# PWRSUPPLY.net
KiCad netlist of a schematic drawn in Altium Designer
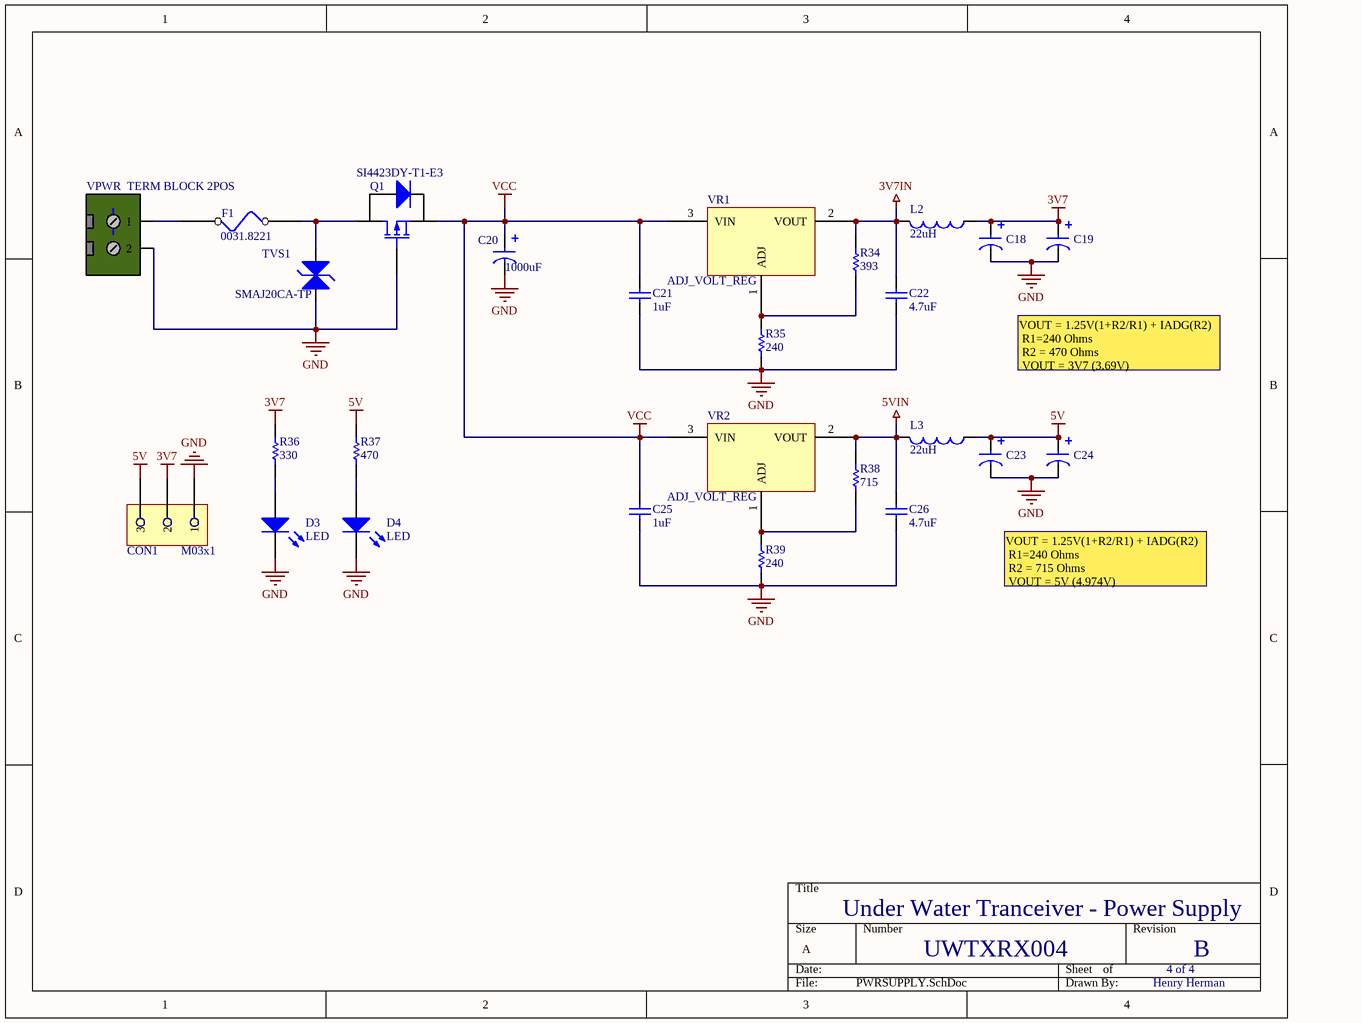
[diagram p0: PWRSUPPLY.SchDoc]

(export (version "E")
  (design (tool "Eeschema 10.0.6"))
  (components
    (comp (ref "C18")
      (value "CAP_POL")
      (footprint "SM/C_POL_0805")
      (description "CAP")
      (libsource (lib "Henry1_20_2010") (part "CAP_POL"))
    )
    (comp (ref "C19")
      (value "CAP_POL")
      (footprint "SM/C_POL_0805")
      (description "CAP")
      (libsource (lib "Henry1_20_2010") (part "CAP_POL"))
    )
    (comp (ref "C20")
      (value "CAP_POL")
      (footprint "CAP-CAN-SMD-POL-12.5mmDia")
      (description "CAP")
      (fields (field (name "LABEL") "1000uF"))
      (libsource (lib "Henry1_20_2010") (part "CAP_POL"))
    )
    (comp (ref "C21")
      (value "1uF")
      (footprint "SM/C_0805")
      (description "CAP")
      (libsource (lib "Henry1_20_2010") (part "CAP"))
    )
    (comp (ref "C22")
      (value "4.7uF")
      (footprint "SM/C_0805")
      (description "CAP")
      (libsource (lib "Henry1_20_2010") (part "CAP"))
    )
    (comp (ref "C23")
      (value "CAP_POL")
      (footprint "SM/C_POL_0805")
      (description "CAP")
      (libsource (lib "Henry1_20_2010") (part "CAP_POL"))
    )
    (comp (ref "C24")
      (value "CAP_POL")
      (footprint "SM/C_POL_0805")
      (description "CAP")
      (libsource (lib "Henry1_20_2010") (part "CAP_POL"))
    )
    (comp (ref "C25")
      (value "1uF")
      (footprint "SM/C_0805")
      (description "CAP")
      (libsource (lib "Henry1_20_2010") (part "CAP"))
    )
    (comp (ref "C26")
      (value "4.7uF")
      (footprint "SM/C_0805")
      (description "CAP")
      (libsource (lib "Henry1_20_2010") (part "CAP"))
    )
    (comp (ref "CON1") (value "M03x1") (footprint "M03x1") (libsource (lib "Henry1_20_2010") (part "M03x1")))
    (comp (ref "D3") (value "LED") (footprint "LED-0805") (libsource (lib "Henry1_20_2010") (part "LED")))
    (comp (ref "D4") (value "LED") (footprint "LED-0805") (libsource (lib "Henry1_20_2010") (part "LED")))
    (comp (ref "F1")
      (value "0031.8221")
      (footprint "SCHURTER/SMD/2 PADS/0031.8221")
      (description "FUSEHOLDER BLACK FOR SMD 5X20MM")
      (libsource (lib "FriedParts") (part "FUSE"))
    )
    (comp (ref "L2")
      (value "22uH")
      (footprint "G_JMETRIC/TDK/SLE10145")
      (description "INDUCTOR SHIELD PWR 22UH 10145")
      (fields (field (name "MFRPARTNUM") "SLF10145T-220M1R9-PF"))
      (libsource (lib "FriedParts") (part "INDUCTOR"))
    )
    (comp (ref "L3")
      (value "22uH")
      (footprint "G_JMETRIC/TDK/SLE10145")
      (description "INDUCTOR SHIELD PWR 22UH 10145")
      (fields (field (name "MFRPARTNUM") "SLF10145T-220M1R9-PF"))
      (libsource (lib "FriedParts") (part "INDUCTOR"))
    )
    (comp (ref "Q1")
      (value "SI4423DY-T1-E3")
      (footprint "SOIC-8-Lead-Vishay-PFET")
      (description "mosfet,p ch,20v,10a,8soic; transistor polarity:p channel;")
      (libsource (lib "FriedParts") (part "P-Channel 20V D-S MOSFET"))
    )
    (comp (ref "R34")
      (value "393")
      (footprint "SM/R_0805")
      (description "Resistor")
      (fields (field (name "Comment") "Res") (field (name "PUBLISHER") "Altium Limited"))
      (libsource (lib "Henry1_20_2010") (part "Res"))
    )
    (comp (ref "R35")
      (value "240")
      (footprint "SM/R_0805")
      (description "Resistor")
      (fields (field (name "Comment") "Res") (field (name "PUBLISHER") "Altium Limited"))
      (libsource (lib "Henry1_20_2010") (part "Res"))
    )
    (comp (ref "R36")
      (value "330")
      (footprint "SM/R_0805")
      (description "Resistor")
      (fields (field (name "Comment") "Res") (field (name "PUBLISHER") "Altium Limited"))
      (libsource (lib "Henry1_20_2010") (part "Res"))
    )
    (comp (ref "R37")
      (value "470")
      (footprint "SM/R_0805")
      (description "Resistor")
      (fields (field (name "Comment") "Res") (field (name "PUBLISHER") "Altium Limited"))
      (libsource (lib "Henry1_20_2010") (part "Res"))
    )
    (comp (ref "R38")
      (value "715")
      (footprint "SM/R_0805")
      (description "Resistor")
      (fields (field (name "Comment") "Res") (field (name "PUBLISHER") "Altium Limited"))
      (libsource (lib "Henry1_20_2010") (part "Res"))
    )
    (comp (ref "R39")
      (value "240")
      (footprint "SM/R_0805")
      (description "Resistor")
      (fields (field (name "Comment") "Res") (field (name "PUBLISHER") "Altium Limited"))
      (libsource (lib "Henry1_20_2010") (part "Res"))
    )
    (comp (ref "TVS1")
      (value "SMAJ20CA-TP")
      (footprint "D0-214AC")
      (description "TVS 400W 12V BIDIRECT SMA")
      (fields (field (name "MFRPARTNUM") "SMAJ12CA-TP"))
      (libsource (lib "FriedParts") (part "SMAJ12CA-TPMC"))
    )
    (comp (ref "VPWR")
      (value "TERM BLOCK 2POS")
      (footprint "Conn-ScrewTerminal-2pin-Phoenix")
      (libsource (lib "Henry1_20_2010") (part "2Pin-PhoenixTerminalBlock"))
    )
    (comp (ref "VR1")
      (value "ADJ_VOLT_REG")
      (footprint "LM317-SOT233-POS-ADJ-VOLT_REG")
      (libsource (lib "Henry1_20_2010") (part "ADJ_VOLT_REG"))
    )
    (comp (ref "VR2")
      (value "ADJ_VOLT_REG")
      (footprint "LM317-SOT233-POS-ADJ-VOLT_REG")
      (libsource (lib "Henry1_20_2010") (part "ADJ_VOLT_REG"))
    )
  )
  (nets
    (net (code "1") (name "3V7") (class "Default")
      (node (ref "C18") (pin "1") (pinfunction "1_1") (pintype "passive"))
      (node (ref "C19") (pin "1") (pinfunction "1_1") (pintype "passive"))
      (node (ref "CON1") (pin "2") (pinfunction "2_2") (pintype "passive"))
      (node (ref "L2") (pin "1") (pinfunction "1_1") (pintype "passive"))
      (node (ref "R36") (pin "1") (pinfunction "1_1") (pintype "passive"))
    )
    (net (code "2") (name "3V7IN") (class "Default")
      (node (ref "C22") (pin "2") (pinfunction "2_2") (pintype "passive"))
      (node (ref "L2") (pin "2") (pinfunction "2_2") (pintype "passive"))
      (node (ref "R34") (pin "2") (pinfunction "2_2") (pintype "passive"))
      (node (ref "VR1") (pin "2") (pinfunction "VOUT_2") (pintype "passive"))
    )
    (net (code "3") (name "5V") (class "Default")
      (node (ref "C23") (pin "1") (pinfunction "1_1") (pintype "passive"))
      (node (ref "C24") (pin "1") (pinfunction "1_1") (pintype "passive"))
      (node (ref "CON1") (pin "3") (pinfunction "3_3") (pintype "passive"))
      (node (ref "L3") (pin "1") (pinfunction "1_1") (pintype "passive"))
      (node (ref "R37") (pin "1") (pinfunction "1_1") (pintype "passive"))
    )
    (net (code "4") (name "5VIN") (class "Default")
      (node (ref "C26") (pin "2") (pinfunction "2_2") (pintype "passive"))
      (node (ref "L3") (pin "2") (pinfunction "2_2") (pintype "passive"))
      (node (ref "R38") (pin "1") (pinfunction "1_1") (pintype "passive"))
      (node (ref "VR2") (pin "2") (pinfunction "VOUT_2") (pintype "passive"))
    )
    (net (code "5") (name "GND") (class "Default")
      (node (ref "C18") (pin "2") (pinfunction "2_2") (pintype "passive"))
      (node (ref "C19") (pin "2") (pinfunction "2_2") (pintype "passive"))
      (node (ref "C20") (pin "2") (pinfunction "2_2") (pintype "passive"))
      (node (ref "C21") (pin "1") (pinfunction "1_1") (pintype "passive"))
      (node (ref "C22") (pin "1") (pinfunction "1_1") (pintype "passive"))
      (node (ref "C23") (pin "2") (pinfunction "2_2") (pintype "passive"))
      (node (ref "C24") (pin "2") (pinfunction "2_2") (pintype "passive"))
      (node (ref "C25") (pin "1") (pinfunction "1_1") (pintype "passive"))
      (node (ref "C26") (pin "1") (pinfunction "1_1") (pintype "passive"))
      (node (ref "CON1") (pin "1") (pinfunction "1_1") (pintype "passive"))
      (node (ref "D3") (pin "2") (pinfunction "K_2") (pintype "passive"))
      (node (ref "D4") (pin "2") (pinfunction "K_2") (pintype "passive"))
      (node (ref "Q1") (pin "G") (pinfunction "G_G") (pintype "passive"))
      (node (ref "R35") (pin "1") (pinfunction "1_1") (pintype "passive"))
      (node (ref "R39") (pin "1") (pinfunction "1_1") (pintype "passive"))
      (node (ref "TVS1") (pin "C") (pinfunction "1_C") (pintype "passive"))
      (node (ref "VPWR") (pin "2") (pinfunction "2_2") (pintype "passive"))
    )
    (net (code "6") (name "Net-(D3-A)") (class "Default")
      (node (ref "D3") (pin "1") (pinfunction "A_1") (pintype "passive"))
      (node (ref "R36") (pin "2") (pinfunction "2_2") (pintype "passive"))
    )
    (net (code "7") (name "Net-(D4-A)") (class "Default")
      (node (ref "D4") (pin "1") (pinfunction "A_1") (pintype "passive"))
      (node (ref "R37") (pin "2") (pinfunction "2_2") (pintype "passive"))
    )
    (net (code "8") (name "Net-(F1-Pad1)") (class "Default")
      (node (ref "F1") (pin "1") (pinfunction "1_1") (pintype "passive"))
      (node (ref "VPWR") (pin "1") (pinfunction "1_1") (pintype "passive"))
    )
    (net (code "9") (name "Net-(TVS1-2)") (class "Default")
      (node (ref "F1") (pin "2") (pinfunction "2_2") (pintype "passive"))
      (node (ref "Q1") (pin "D") (pinfunction "D_D") (pintype "passive"))
      (node (ref "TVS1") (pin "A") (pinfunction "2_A") (pintype "passive"))
    )
    (net (code "10") (name "Net-(VR1-ADJ)") (class "Default")
      (node (ref "R34") (pin "1") (pinfunction "1_1") (pintype "passive"))
      (node (ref "R35") (pin "2") (pinfunction "2_2") (pintype "passive"))
      (node (ref "VR1") (pin "1") (pinfunction "ADJ_1") (pintype "passive"))
    )
    (net (code "11") (name "Net-(VR2-ADJ)") (class "Default")
      (node (ref "R38") (pin "2") (pinfunction "2_2") (pintype "passive"))
      (node (ref "R39") (pin "2") (pinfunction "2_2") (pintype "passive"))
      (node (ref "VR2") (pin "1") (pinfunction "ADJ_1") (pintype "passive"))
    )
    (net (code "12") (name "VCC") (class "Default")
      (node (ref "C20") (pin "1") (pinfunction "1_1") (pintype "passive"))
      (node (ref "C21") (pin "2") (pinfunction "2_2") (pintype "passive"))
      (node (ref "C25") (pin "2") (pinfunction "2_2") (pintype "passive"))
      (node (ref "Q1") (pin "S") (pinfunction "S_S") (pintype "passive"))
      (node (ref "VR1") (pin "3") (pinfunction "VIN_3") (pintype "passive"))
      (node (ref "VR2") (pin "3") (pinfunction "VIN_3") (pintype "passive"))
    )
  )
)
